# PWM_5_8A_30V.net
KiCad netlist of a schematic drawn in Altium Designer
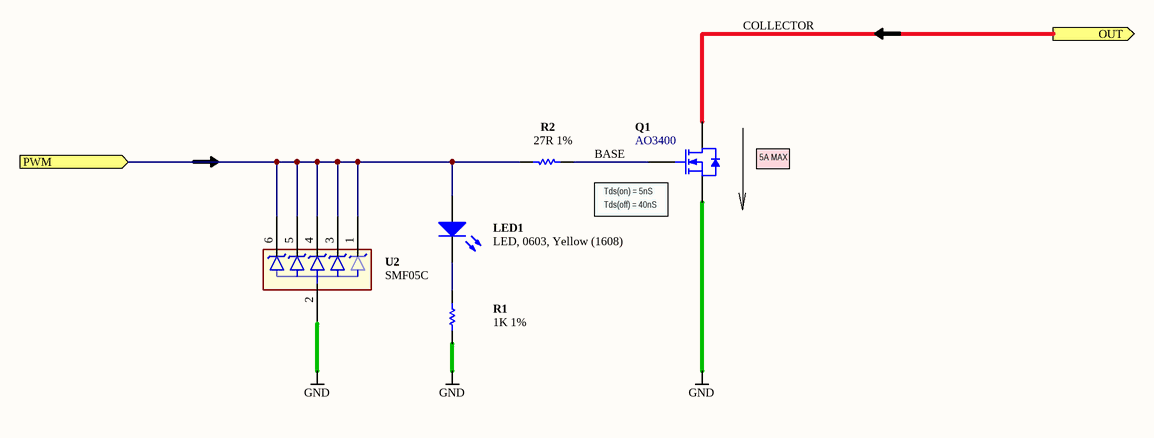
[diagram p0: PWM_5.8A_30V.SchDoc]

(export (version "E")
  (design (tool "Eeschema 10.0.6"))
  (components
    (comp (ref "LED1")
      (value "LED, 0603, Yellow (1608)")
      (footprint "0603LED_YELLOW")
      (libsource (lib "AltiumDesignLibrary") (part "DIO-LED-1S"))
    )
    (comp (ref "Q1")
      (value "AO3400")
      (footprint "SOT95P230-3D")
      (description "N-channel Enhancement Mode Field-effect Transistor;  5.8A/30V")
      (libsource (lib "AltiumDesignLibrary") (part "N-Channel-FET"))
    )
    (comp (ref "R1")
      (value "1K 1%")
      (footprint "RESC1005-STAR")
      (description "Resistor, 1K 1% 0402 (1005)")
      (fields (field (name "TOLERANCE") "1 %"))
      (libsource (lib "AltiumDesignLibrary") (part "RES"))
    )
    (comp (ref "R2")
      (value "27R 1%")
      (footprint "RESC1005-STAR")
      (description "Resistor, 27R 1% 0402 (1005)")
      (fields (field (name "TOLERANCE") "1%"))
      (libsource (lib "AltiumDesignLibrary") (part "RES"))
    )
    (comp (ref "U2")
      (value "SMF05C")
      (footprint "SC70_6L")
      (description "TVS Diode Array  For ESD and Latch-Up Protection")
      (libsource (lib "AltiumDesignLibrary") (part "SMF05C"))
    )
  )
  (nets
    (net (code "1") (name "/BASE") (class "Default")
      (node (ref "Q1") (pin "1") (pinfunction "G_1") (pintype "passive"))
      (node (ref "R2") (pin "2") (pinfunction "2_2") (pintype "passive"))
    )
    (net (code "2") (name "/COLLECTOR") (class "Default")
      (node (ref "Q1") (pin "2") (pinfunction "D_2") (pintype "passive"))
    )
    (net (code "3") (name "/PWM") (class "Default")
      (node (ref "LED1") (pin "1") (pinfunction "A_1") (pintype "passive"))
      (node (ref "R2") (pin "1") (pinfunction "1_1") (pintype "passive"))
      (node (ref "U2") (pin "1") (pinfunction "1_1") (pintype "passive"))
      (node (ref "U2") (pin "3") (pinfunction "3_3") (pintype "passive"))
      (node (ref "U2") (pin "4") (pinfunction "4_4") (pintype "passive"))
      (node (ref "U2") (pin "5") (pinfunction "5_5") (pintype "passive"))
      (node (ref "U2") (pin "6") (pinfunction "6_6") (pintype "passive"))
    )
    (net (code "4") (name "GND") (class "Default")
      (node (ref "Q1") (pin "3") (pinfunction "S_3") (pintype "passive"))
      (node (ref "R1") (pin "1") (pinfunction "1_1") (pintype "passive"))
      (node (ref "U2") (pin "2") (pinfunction "2_2") (pintype "passive"))
    )
    (net (code "5") (name "Net-(LED1-K)") (class "Default")
      (node (ref "LED1") (pin "2") (pinfunction "K_2") (pintype "passive"))
      (node (ref "R1") (pin "2") (pinfunction "2_2") (pintype "passive"))
    )
  )
)
